# LED_Lamp_Interfaces.net
KiCad netlist of a schematic drawn in Altium Designer
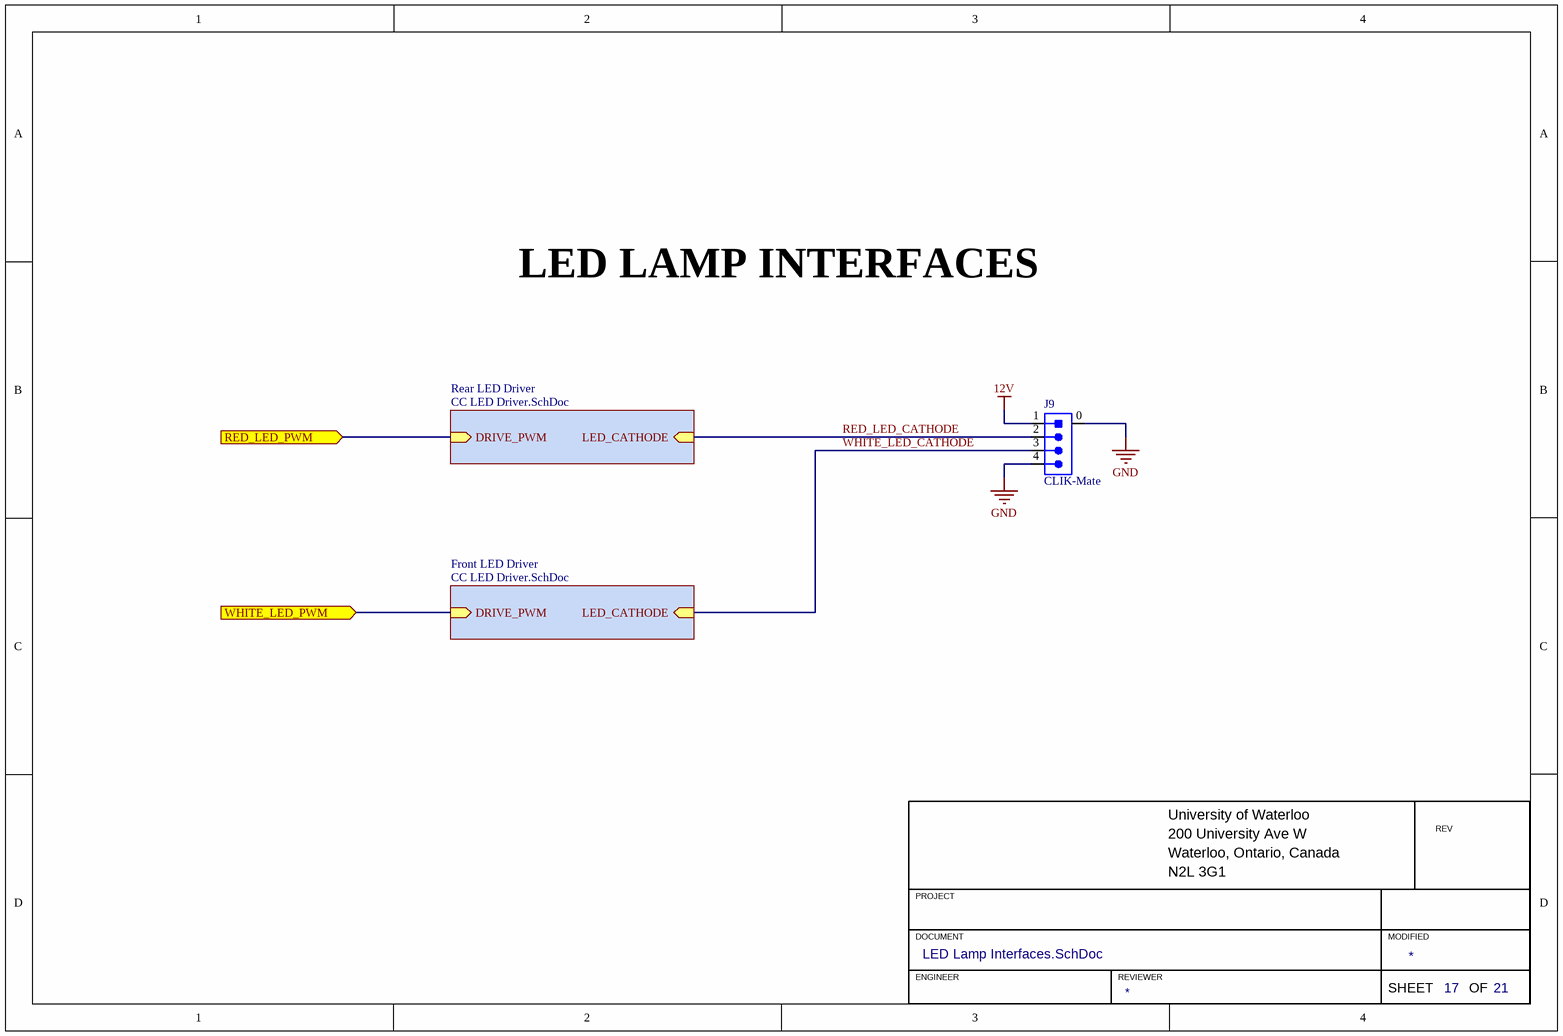
[diagram p0: LED Lamp Interfaces.SchDoc]

(export (version "E")
  (design (tool "Eeschema 10.0.6"))
  (components
    (comp (ref "J9")
      (value "CON_4M_SM_RA")
      (footprint "MOLEX-5025850470")
      (description "CONN HEADER SMD RIGHT ANGLE 1.5 MM PITCH")
      (fields (field (name "FAMILY") "CLIK-Mate"))
      (libsource (lib "Personal_Schematic_Library_2022") (part "CON_4M_SM_RA"))
    )
  )
  (nets
    (net (code "1") (name "/RED_LED_CATHODE") (class "Default")
      (node (ref "J9") (pin "2") (pinfunction "2_2") (pintype "passive"))
    )
    (net (code "3") (name "/WHITE_LED_CATHODE") (class "Default")
      (node (ref "J9") (pin "3") (pinfunction "3_3") (pintype "passive"))
    )
    (net (code "5") (name "12V") (class "Default")
      (node (ref "J9") (pin "1") (pinfunction "1_1") (pintype "passive"))
    )
    (net (code "6") (name "GND") (class "Default")
      (node (ref "J9") (pin "0") (pinfunction "0_0") (pintype "passive"))
      (node (ref "J9") (pin "4") (pinfunction "4_4") (pintype "passive"))
    )
  )
)
